# Flash_-_M25P32-VMW6TG.net
KiCad netlist of a schematic drawn in Altium Designer
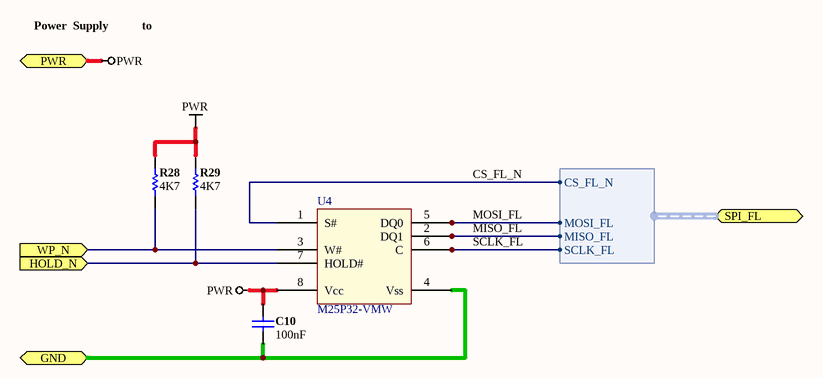
[diagram p0: Flash - M25P32-VMW6TG.SchDoc]

(export (version "E")
  (design (tool "Eeschema 10.0.6"))
  (components
    (comp (ref "C10")
      (value "100nF")
      (footprint "CAPC0402(1005)60_L")
      (fields
        (field (name "TOLERANCE") "±10%")
        (field (name "MANUFACTURER PART NUMBER") "C0402C104K8PACTU")
        (field (name "Comment") "CAP 100nF 16V 0402(1005)")
      )
      (libsource (lib "Component_Database") (part "CAP_NP"))
    )
    (comp (ref "R28")
      (value "4K7")
      (footprint "RESC0402(1005)40_L")
      (fields
        (field (name "POWER") "1/16 W")
        (field (name "MANUFACTURER PART NUMBER") "CR0402-FX-4701GLFDKR-ND")
      )
      (libsource (lib "Component_Database") (part "RES"))
    )
    (comp (ref "R29")
      (value "4K7")
      (footprint "RESC0402(1005)40_L")
      (fields
        (field (name "POWER") "1/16 W")
        (field (name "MANUFACTURER PART NUMBER") "CR0402-FX-4701GLFDKR-ND")
      )
      (libsource (lib "Component_Database") (part "RES"))
    )
    (comp (ref "U4")
      (value "M25P32-VMW")
      (footprint "SOIC-8W")
      (libsource (lib "W25P32-VMW6TG") (part "M25P32-VMW6TG"))
    )
  )
  (nets
    (net (code "2") (name "/CS_FL_N") (class "Default")
      (node (ref "U4") (pin "1") (pinfunction "S#_1") (pintype "passive"))
    )
    (net (code "3") (name "/GND") (class "Default")
      (node (ref "C10") (pin "2") (pinfunction "2_2") (pintype "passive"))
      (node (ref "U4") (pin "4") (pinfunction "Vss_4") (pintype "passive"))
    )
    (net (code "4") (name "/HOLD_N") (class "Default")
      (node (ref "R29") (pin "1") (pinfunction "1_1") (pintype "passive"))
      (node (ref "U4") (pin "7") (pinfunction "HOLD#_7") (pintype "passive"))
    )
    (net (code "5") (name "/MISO_FL") (class "Default")
      (node (ref "U4") (pin "2") (pinfunction "DQ1_2") (pintype "passive"))
    )
    (net (code "6") (name "/MOSI_FL") (class "Default")
      (node (ref "U4") (pin "5") (pinfunction "DQ0_5") (pintype "passive"))
    )
    (net (code "7") (name "/SCLK_FL") (class "Default")
      (node (ref "U4") (pin "6") (pinfunction "C_6") (pintype "passive"))
    )
    (net (code "8") (name "/WP_N") (class "Default")
      (node (ref "R28") (pin "1") (pinfunction "1_1") (pintype "passive"))
      (node (ref "U4") (pin "3") (pinfunction "W#_3") (pintype "passive"))
    )
    (net (code "10") (name "PWR") (class "Default")
      (node (ref "C10") (pin "1") (pinfunction "1_1") (pintype "passive"))
      (node (ref "R28") (pin "2") (pinfunction "2_2") (pintype "passive"))
      (node (ref "R29") (pin "2") (pinfunction "2_2") (pintype "passive"))
      (node (ref "U4") (pin "8") (pinfunction "Vcc_8") (pintype "passive"))
    )
  )
)
